# LMR514205V.net
KiCad netlist of a schematic drawn in Altium Designer
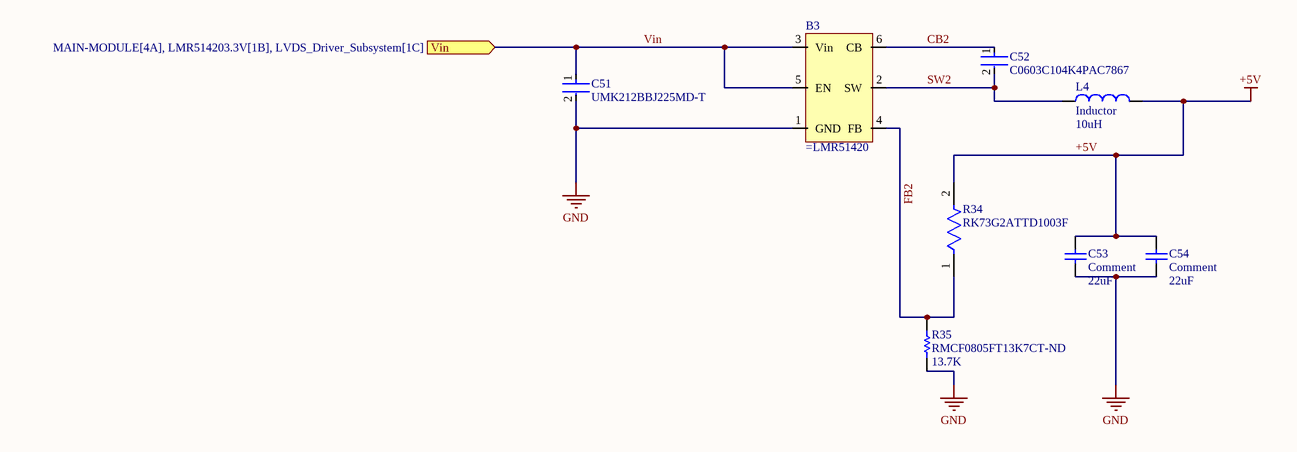
[diagram p0: LMR514205V.SchDoc]

(export (version "E")
  (design (tool "Eeschema 10.0.6"))
  (components
    (comp (ref "B3") (value "~") (footprint "LMR51420IC") (libsource (lib "LMR51420") (part "Component_1")))
    (comp (ref "C51")
      (value "UMK212BBJ225MD-T")
      (footprint "FP-0805-L_2_0_0_2-W_1_25-IPC_A")
      (description "Multilayer Ceramic Capacitor 2.2uF 50V X5R 20% SMD 0803 T/R")
      (fields (field (name "TOLERANCE") "20%"))
      (libsource (lib "Altium Content Vault") (part "02cd4be3c70576c341d710602a673aa"))
    )
    (comp (ref "C52")
      (value "C0603C104K4PAC7867")
      (footprint "CAP CER 0.1UF 16V X7R 0603")
      (description "CAP CER 0.1UF 16V X5R 0603")
      (fields
        (field (name "OCTOPART") "https://octopart.com/c0603c104k4pactu-kemet-12592163")
        (field (name "MANUFACTURER") "KEMET")
      )
      (libsource (lib "Miscellaneous Devices") (part "b4654b650e69147ec39a6b967a45e02"))
    )
    (comp (ref "C53")
      (value "Comment")
      (footprint "Cap22uF_C1206C226M4PAC7800")
      (description "Capacitor")
      (fields (field (name "ALTIUM_VALUE") "22uF") (field (name "PUBLISHER") "Altium Limited"))
      (libsource (lib "Miscellaneous Devices") (part "Cap"))
    )
    (comp (ref "C54")
      (value "Comment")
      (footprint "Cap22uF_C1206C226M4PAC7800")
      (description "Capacitor")
      (fields (field (name "ALTIUM_VALUE") "22uF") (field (name "PUBLISHER") "Altium Limited"))
      (libsource (lib "Miscellaneous Devices") (part "Cap"))
    )
    (comp (ref "L4")
      (value "Inductor")
      (footprint "MSS1246H-103MED 10uH")
      (fields (field (name "ALTIUM_VALUE") "10uH") (field (name "PUBLISHER") "Altium Limited"))
      (libsource (lib "Miscellaneous Devices") (part "Inductor"))
    )
    (comp (ref "R34")
      (value "RK73G2ATTD1003F")
      (footprint "FP-RK73G2A-IPC_A")
      (description "100kΩ ±1% 0.125W Chip Resistor 0805 Thick Film AEC-Q200 Qualified")
      (fields (field (name "TOLERANCE") "1%"))
      (libsource (lib "Altium Content Vault") (part "1029c3af85768c4190bb7ad29bc67b5"))
    )
    (comp (ref "R35")
      (value "RMCF0805FT13K7CT-ND")
      (footprint "RMCF0805FT13K7_13.7k")
      (description "Resistor")
      (fields (field (name "ALTIUM_VALUE") "13.7K") (field (name "PUBLISHER") "Altium Limited"))
      (libsource (lib "Miscellaneous Devices") (part "Res1"))
    )
  )
  (nets
    (net (code "1") (name "+5V") (class "Default")
      (node (ref "C53") (pin "2") (pinfunction "2_2") (pintype "passive"))
      (node (ref "C54") (pin "2") (pinfunction "2_2") (pintype "passive"))
      (node (ref "L4") (pin "2") (pinfunction "2_2") (pintype "passive"))
      (node (ref "R34") (pin "2") (pinfunction "2_2") (pintype "passive"))
    )
    (net (code "2") (name "/CB2") (class "Default")
      (node (ref "B3") (pin "6") (pinfunction "CB_6") (pintype "passive"))
      (node (ref "C52") (pin "1") (pinfunction "1_1") (pintype "passive"))
    )
    (net (code "3") (name "/FB2") (class "Default")
      (node (ref "B3") (pin "4") (pinfunction "FB_4") (pintype "passive"))
      (node (ref "R34") (pin "1") (pinfunction "1_1") (pintype "passive"))
      (node (ref "R35") (pin "2") (pinfunction "2_2") (pintype "passive"))
    )
    (net (code "4") (name "/SW2") (class "Default")
      (node (ref "B3") (pin "2") (pinfunction "SW_2") (pintype "passive"))
      (node (ref "C52") (pin "2") (pinfunction "2_2") (pintype "passive"))
      (node (ref "L4") (pin "1") (pinfunction "1_1") (pintype "passive"))
    )
    (net (code "5") (name "/Vin") (class "Default")
      (node (ref "B3") (pin "3") (pinfunction "Vin_3") (pintype "passive"))
      (node (ref "B3") (pin "5") (pinfunction "EN_5") (pintype "passive"))
      (node (ref "C51") (pin "1") (pinfunction "1_1") (pintype "passive"))
    )
    (net (code "6") (name "GND") (class "Default")
      (node (ref "B3") (pin "1") (pinfunction "GND_1") (pintype "passive"))
      (node (ref "C51") (pin "2") (pinfunction "2_2") (pintype "passive"))
      (node (ref "C53") (pin "1") (pinfunction "1_1") (pintype "passive"))
      (node (ref "C54") (pin "1") (pinfunction "1_1") (pintype "passive"))
      (node (ref "R35") (pin "1") (pinfunction "1_1") (pintype "passive"))
    )
  )
)
